# czujnik_tetna.net
KiCad netlist of a schematic drawn in Altium Designer
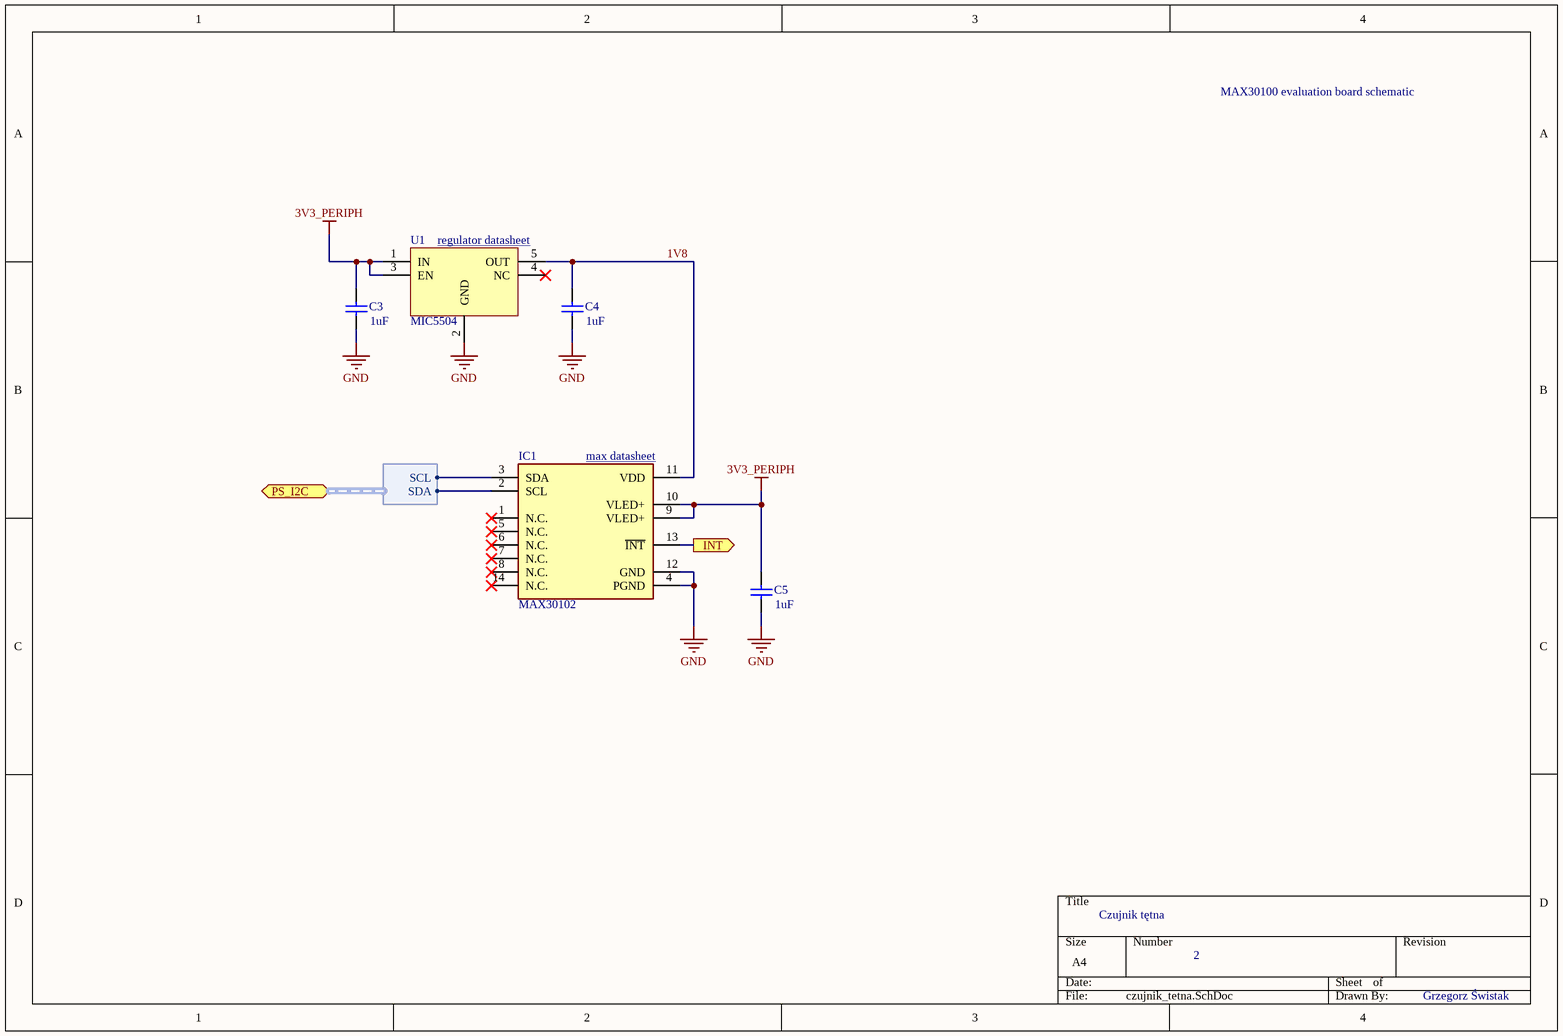
[diagram p0: czujnik_tetna.SchDoc]

(export (version "E")
  (design (tool "Eeschema 10.0.6"))
  (components
    (comp (ref "C3")
      (value "1uF")
      (footprint "cap-0603")
      (description "Capacitor")
      (fields (field (name "Comment") "Cap") (field (name "PUBLISHER") "Altium Limited"))
      (libsource (lib "Miscellaneous Devices") (part "Cap"))
    )
    (comp (ref "C4")
      (value "1uF")
      (footprint "cap-0603")
      (description "Capacitor")
      (fields (field (name "Comment") "Cap") (field (name "PUBLISHER") "Altium Limited"))
      (libsource (lib "Miscellaneous Devices") (part "Cap"))
    )
    (comp (ref "C5")
      (value "1uF")
      (footprint "cap-0603")
      (description "Capacitor")
      (fields (field (name "Comment") "Cap") (field (name "PUBLISHER") "Altium Limited"))
      (libsource (lib "Miscellaneous Devices") (part "Cap"))
    )
    (comp (ref "IC1")
      (value "MAX30102")
      (footprint "MAX30102EFDT")
      (description "https://datasheets.maximintegrated.com/en/ds/MAX30102.pdf")
      (fields
        (field (name "MANUFACTURER_PART_NUMBER") "MAX30102EFD+T")
        (field (name "MOUSER PART NUMBER") "700-MAX30102EFD+T")
      )
      (libsource (lib "lib") (part "MAX30102EFD+T"))
    )
    (comp (ref "U1")
      (value "MIC5504")
      (footprint "SOT23-5")
      (description "http://ww1.microchip.com/downloads/en/DeviceDoc/21813F.pdf")
      (libsource (lib "lib") (part "MIC5504"))
    )
  )
  (nets
    (net (code "2") (name "/1V8") (class "Default")
      (node (ref "C4") (pin "2") (pinfunction "2_2") (pintype "passive"))
      (node (ref "IC1") (pin "11") (pinfunction "VDD_11") (pintype "passive"))
      (node (ref "U1") (pin "5") (pinfunction "OUT_5") (pintype "passive"))
    )
    (net (code "3") (name "/INT") (class "Default")
      (node (ref "IC1") (pin "13") (pinfunction "~{INT}_13") (pintype "passive"))
    )
    (net (code "4") (name "/SCL") (class "Default")
      (node (ref "IC1") (pin "3") (pinfunction "SDA_3") (pintype "passive"))
    )
    (net (code "5") (name "/SDA") (class "Default")
      (node (ref "IC1") (pin "2") (pinfunction "SCL_2") (pintype "passive"))
    )
    (net (code "7") (name "3V3_PERIPH") (class "Default")
      (node (ref "C3") (pin "2") (pinfunction "2_2") (pintype "passive"))
      (node (ref "C5") (pin "2") (pinfunction "2_2") (pintype "passive"))
      (node (ref "IC1") (pin "10") (pinfunction "VLED+_10") (pintype "passive"))
      (node (ref "IC1") (pin "9") (pinfunction "VLED+_9") (pintype "passive"))
      (node (ref "U1") (pin "1") (pinfunction "IN_1") (pintype "passive"))
      (node (ref "U1") (pin "3") (pinfunction "EN_3") (pintype "passive"))
    )
    (net (code "8") (name "GND") (class "Default")
      (node (ref "C3") (pin "1") (pinfunction "1_1") (pintype "passive"))
      (node (ref "C4") (pin "1") (pinfunction "1_1") (pintype "passive"))
      (node (ref "C5") (pin "1") (pinfunction "1_1") (pintype "passive"))
      (node (ref "IC1") (pin "12") (pinfunction "GND_12") (pintype "passive"))
      (node (ref "IC1") (pin "4") (pinfunction "PGND_4") (pintype "passive"))
      (node (ref "U1") (pin "2") (pinfunction "GND_2") (pintype "passive"))
    )
    (net (code "9") (name "unconnected-(IC1-N.C.-Pad1)") (class "Default")
      (node (ref "IC1") (pin "1") (pinfunction "N.C._1") (pintype "passive+no_connect"))
    )
    (net (code "10") (name "unconnected-(IC1-N.C.-Pad5)") (class "Default")
      (node (ref "IC1") (pin "5") (pinfunction "N.C._5") (pintype "passive+no_connect"))
    )
    (net (code "11") (name "unconnected-(IC1-N.C.-Pad6)") (class "Default")
      (node (ref "IC1") (pin "6") (pinfunction "N.C._6") (pintype "passive+no_connect"))
    )
    (net (code "12") (name "unconnected-(IC1-N.C.-Pad7)") (class "Default")
      (node (ref "IC1") (pin "7") (pinfunction "N.C._7") (pintype "passive+no_connect"))
    )
    (net (code "13") (name "unconnected-(IC1-N.C.-Pad8)") (class "Default")
      (node (ref "IC1") (pin "8") (pinfunction "N.C._8") (pintype "passive+no_connect"))
    )
    (net (code "14") (name "unconnected-(IC1-N.C.-Pad14)") (class "Default")
      (node (ref "IC1") (pin "14") (pinfunction "N.C._14") (pintype "passive+no_connect"))
    )
    (net (code "15") (name "unconnected-(U1-NC-Pad4)") (class "Default")
      (node (ref "U1") (pin "4") (pinfunction "NC_4") (pintype "passive+no_connect"))
    )
  )
)
